# ina226.net
KiCad netlist of a schematic drawn in Altium Designer
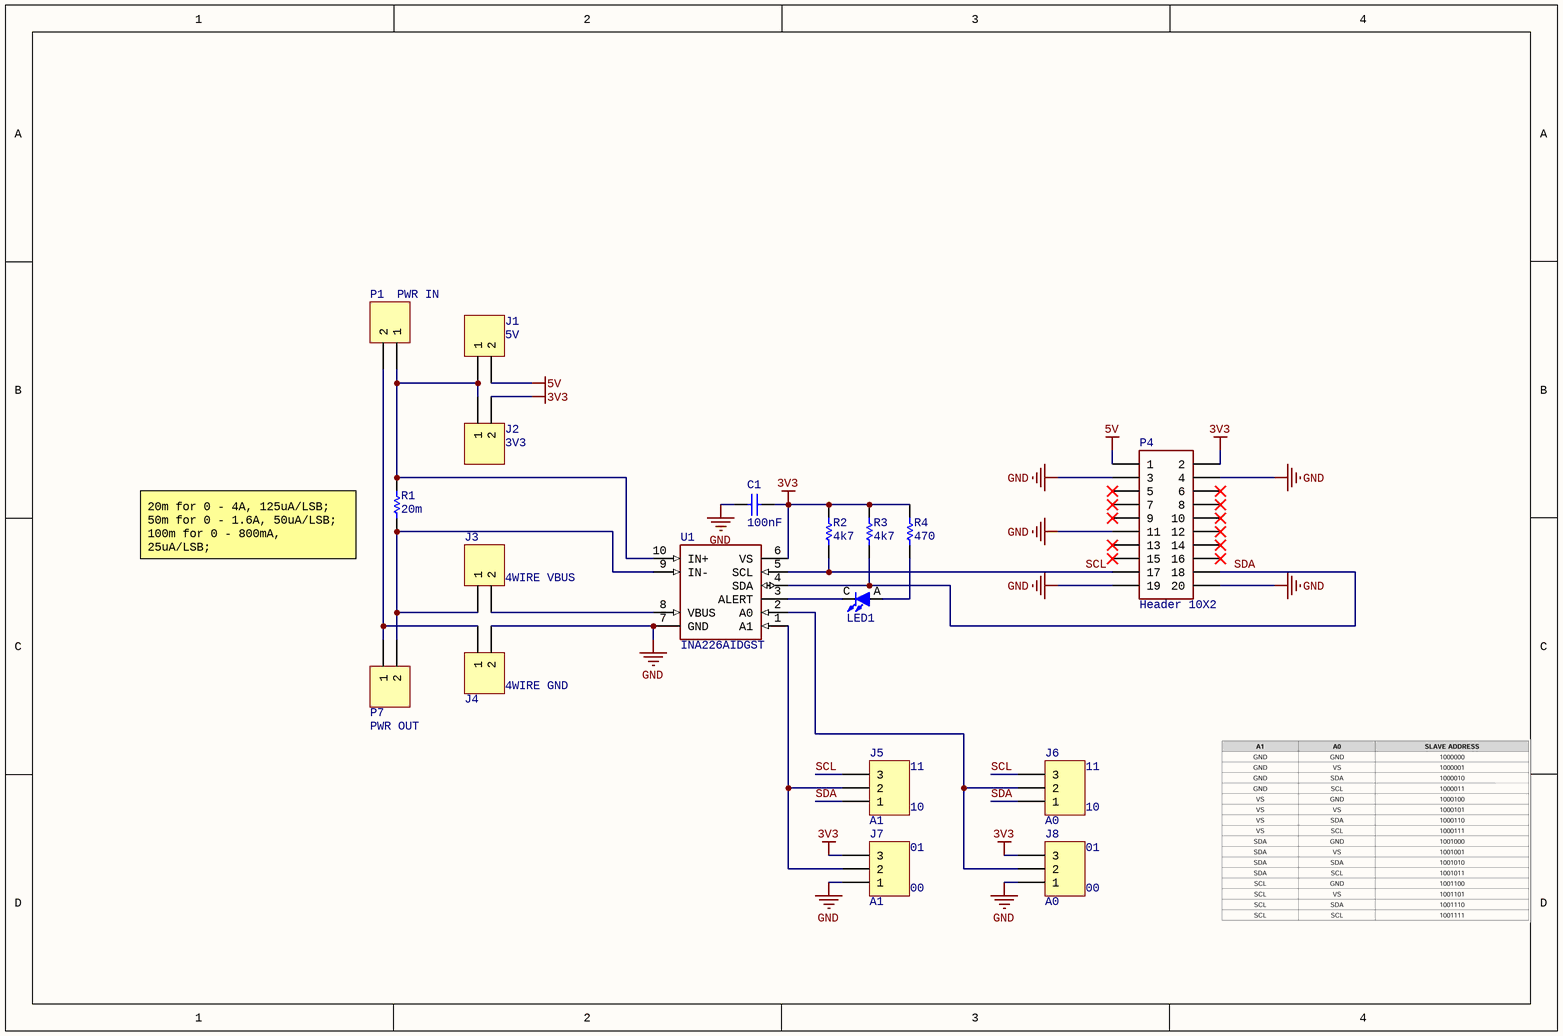
[diagram p0: ina226.SchDoc]

(export (version "E")
  (design (tool "Eeschema 10.0.6"))
  (components
    (comp (ref "C1")
      (value "100nF")
      (footprint "footprints:CAPC100X50X55L25N")
      (description "Capacitor (Semiconductor SIM Model)")
      (fields (field (name "PUBLISHER") "Altium Limited"))
      (libsource (lib "Miscellaneous Devices") (part "Cap Semi"))
    )
    (comp (ref "J1")
      (value "5V")
      (footprint "HDR1X2")
      (description "Header, 2-Pin")
      (fields (field (name "PUBLISHER") "Altium Limited"))
      (libsource (lib "Miscellaneous Connectors") (part "Header 2"))
    )
    (comp (ref "J2")
      (value "3V3")
      (footprint "HDR1X2")
      (description "Header, 2-Pin")
      (fields (field (name "PUBLISHER") "Altium Limited"))
      (libsource (lib "") (part "Header 2_2"))
    )
    (comp (ref "J3")
      (value "4WIRE VBUS")
      (footprint "HDR1X2")
      (description "Header, 2-Pin")
      (fields (field (name "PUBLISHER") "Altium Limited"))
      (libsource (lib "Miscellaneous Connectors") (part "Header 2"))
    )
    (comp (ref "J4")
      (value "4WIRE GND")
      (footprint "HDR1X2")
      (description "Header, 2-Pin")
      (fields (field (name "PUBLISHER") "Altium Limited"))
      (libsource (lib "") (part "Header 2_2"))
    )
    (comp (ref "J5")
      (value "A1")
      (footprint "HDR1X3")
      (description "Header, 3-Pin")
      (fields (field (name "PUBLISHER") "Altium Limited"))
      (libsource (lib "Miscellaneous Connectors") (part "Header 3"))
    )
    (comp (ref "J6")
      (value "A0")
      (footprint "HDR1X3")
      (description "Header, 3-Pin")
      (fields (field (name "PUBLISHER") "Altium Limited"))
      (libsource (lib "Miscellaneous Connectors") (part "Header 3"))
    )
    (comp (ref "J7")
      (value "A1")
      (footprint "HDR1X3")
      (description "Header, 3-Pin")
      (fields (field (name "PUBLISHER") "Altium Limited"))
      (libsource (lib "Miscellaneous Connectors") (part "Header 3"))
    )
    (comp (ref "J8")
      (value "A0")
      (footprint "HDR1X3")
      (description "Header, 3-Pin")
      (fields (field (name "PUBLISHER") "Altium Limited"))
      (libsource (lib "Miscellaneous Connectors") (part "Header 3"))
    )
    (comp (ref "LED1")
      (value "蓝灯 正贴")
      (footprint "footprints:LEDC100X50X45L25N")
      (description "贴片LED")
      (libsource (lib "mcontroller") (part "LED-SMD"))
    )
    (comp (ref "P1")
      (value "PWR IN")
      (footprint "footprints:CONN-TH_P3.50_KF250-3.5-2P-1")
      (description "Header, 2-Pin")
      (fields (field (name "PUBLISHER") "Altium Limited"))
      (libsource (lib "") (part "Header 2_1"))
    )
    (comp (ref "P4")
      (value "Header 10X2")
      (footprint "footprints:HDRV20W63P254_10X2_2540X508H860")
      (description "Header, 10-Pin, Dual row")
      (libsource (lib "Sch") (part "Header 10X2"))
    )
    (comp (ref "P7")
      (value "PWR OUT")
      (footprint "footprints:CONN-TH_P3.50_KF250-3.5-2P-1")
      (description "Header, 2-Pin")
      (fields (field (name "PUBLISHER") "Altium Limited"))
      (libsource (lib "") (part "Header 2_2"))
    )
    (comp (ref "R1")
      (value "20m")
      (footprint "footprints:RESC620X325X80L80N-K")
      (description "Resistor")
      (libsource (lib "Miscellaneous Devices") (part "Res1"))
    )
    (comp (ref "R2")
      (value "4k7")
      (footprint "footprints:RESC100X50X35L25N")
      (description "Resistor")
      (fields (field (name "PUBLISHER") "Altium Limited"))
      (libsource (lib "Miscellaneous Devices") (part "Res1"))
    )
    (comp (ref "R3")
      (value "4k7")
      (footprint "footprints:RESC100X50X35L25N")
      (description "Resistor")
      (fields (field (name "PUBLISHER") "Altium Limited"))
      (libsource (lib "Miscellaneous Devices") (part "Res1"))
    )
    (comp (ref "R4")
      (value "470")
      (footprint "footprints:RESC100X50X35L25N")
      (description "Resistor")
      (fields (field (name "PUBLISHER") "Altium Limited"))
      (libsource (lib "Miscellaneous Devices") (part "Res1"))
    )
    (comp (ref "U1")
      (value "INA226AIDGST")
      (footprint "footprints:DGS0010A_N")
      (libsource (lib "Sch") (part "CMP-0704-00057-2"))
    )
  )
  (nets
    (net (code "1") (name "/SCL") (class "Default")
      (node (ref "J5") (pin "3") (pinfunction "3_3") (pintype "passive"))
      (node (ref "J6") (pin "3") (pinfunction "3_3") (pintype "passive"))
      (node (ref "P4") (pin "17") (pinfunction "17_17") (pintype "passive"))
      (node (ref "R2") (pin "1") (pinfunction "1_1") (pintype "passive"))
      (node (ref "U1") (pin "5") (pinfunction "SCL_5") (pintype "input"))
    )
    (net (code "2") (name "/SDA") (class "Default")
      (node (ref "J5") (pin "1") (pinfunction "1_1") (pintype "passive"))
      (node (ref "J6") (pin "1") (pinfunction "1_1") (pintype "passive"))
      (node (ref "P4") (pin "18") (pinfunction "18_18") (pintype "passive"))
      (node (ref "R3") (pin "1") (pinfunction "1_1") (pintype "passive"))
      (node (ref "U1") (pin "4") (pinfunction "SDA_4") (pintype "bidirectional"))
    )
    (net (code "3") (name "3V3") (class "Default")
      (node (ref "C1") (pin "2") (pinfunction "2_2") (pintype "passive"))
      (node (ref "J2") (pin "2") (pinfunction "2_2") (pintype "passive"))
      (node (ref "J7") (pin "3") (pinfunction "3_3") (pintype "passive"))
      (node (ref "J8") (pin "3") (pinfunction "3_3") (pintype "passive"))
      (node (ref "P4") (pin "2") (pinfunction "2_2") (pintype "passive"))
      (node (ref "R2") (pin "2") (pinfunction "2_2") (pintype "passive"))
      (node (ref "R3") (pin "2") (pinfunction "2_2") (pintype "passive"))
      (node (ref "R4") (pin "2") (pinfunction "2_2") (pintype "passive"))
      (node (ref "U1") (pin "6") (pinfunction "VS_6") (pintype "power_in"))
    )
    (net (code "4") (name "5V") (class "Default")
      (node (ref "J1") (pin "2") (pinfunction "2_2") (pintype "passive"))
      (node (ref "P4") (pin "1") (pinfunction "1_1") (pintype "passive"))
    )
    (net (code "5") (name "GND") (class "Default")
      (node (ref "C1") (pin "1") (pinfunction "1_1") (pintype "passive"))
      (node (ref "J4") (pin "2") (pinfunction "2_2") (pintype "passive"))
      (node (ref "J7") (pin "1") (pinfunction "1_1") (pintype "passive"))
      (node (ref "J8") (pin "1") (pinfunction "1_1") (pintype "passive"))
      (node (ref "P4") (pin "11") (pinfunction "11_11") (pintype "passive"))
      (node (ref "P4") (pin "19") (pinfunction "19_19") (pintype "passive"))
      (node (ref "P4") (pin "20") (pinfunction "20_20") (pintype "passive"))
      (node (ref "P4") (pin "3") (pinfunction "3_3") (pintype "passive"))
      (node (ref "P4") (pin "4") (pinfunction "4_4") (pintype "passive"))
      (node (ref "U1") (pin "7") (pinfunction "GND_7") (pintype "power_in"))
    )
    (net (code "6") (name "Net-(J4-Pad1)") (class "Default")
      (node (ref "J4") (pin "1") (pinfunction "1_1") (pintype "passive"))
      (node (ref "P1") (pin "2") (pinfunction "2_2") (pintype "passive"))
      (node (ref "P7") (pin "1") (pinfunction "1_1") (pintype "passive"))
    )
    (net (code "7") (name "Net-(LED1-K)") (class "Default")
      (node (ref "LED1") (pin "C") (pinfunction "K_C") (pintype "passive"))
      (node (ref "U1") (pin "3") (pinfunction "ALERT_3") (pintype "open_collector"))
    )
    (net (code "8") (name "Net-(LED1-PadA)") (class "Default")
      (node (ref "LED1") (pin "A") (pinfunction "A_A") (pintype "passive"))
      (node (ref "R4") (pin "1") (pinfunction "1_1") (pintype "passive"))
    )
    (net (code "9") (name "Net-(U1-A0)") (class "Default")
      (node (ref "J6") (pin "2") (pinfunction "2_2") (pintype "passive"))
      (node (ref "J8") (pin "2") (pinfunction "2_2") (pintype "passive"))
      (node (ref "U1") (pin "2") (pinfunction "A0_2") (pintype "input"))
    )
    (net (code "10") (name "Net-(U1-A1)") (class "Default")
      (node (ref "J5") (pin "2") (pinfunction "2_2") (pintype "passive"))
      (node (ref "J7") (pin "2") (pinfunction "2_2") (pintype "passive"))
      (node (ref "U1") (pin "1") (pinfunction "A1_1") (pintype "input"))
    )
    (net (code "11") (name "Net-(U1-IN+)") (class "Default")
      (node (ref "J1") (pin "1") (pinfunction "1_1") (pintype "passive"))
      (node (ref "J2") (pin "1") (pinfunction "1_1") (pintype "passive"))
      (node (ref "P1") (pin "1") (pinfunction "1_1") (pintype "passive"))
      (node (ref "R1") (pin "2") (pinfunction "2_2") (pintype "passive"))
      (node (ref "U1") (pin "10") (pinfunction "IN+_10") (pintype "input"))
    )
    (net (code "12") (name "Net-(U1-IN-)") (class "Default")
      (node (ref "J3") (pin "1") (pinfunction "1_1") (pintype "passive"))
      (node (ref "P7") (pin "2") (pinfunction "2_2") (pintype "passive"))
      (node (ref "R1") (pin "1") (pinfunction "1_1") (pintype "passive"))
      (node (ref "U1") (pin "9") (pinfunction "IN-_9") (pintype "input"))
    )
    (net (code "13") (name "Net-(U1-VBUS)") (class "Default")
      (node (ref "J3") (pin "2") (pinfunction "2_2") (pintype "passive"))
      (node (ref "U1") (pin "8") (pinfunction "VBUS_8") (pintype "input"))
    )
    (net (code "14") (name "unconnected-(P4-Pad5)") (class "Default")
      (node (ref "P4") (pin "5") (pinfunction "5_5") (pintype "passive+no_connect"))
    )
    (net (code "15") (name "unconnected-(P4-Pad6)") (class "Default")
      (node (ref "P4") (pin "6") (pinfunction "6_6") (pintype "passive+no_connect"))
    )
    (net (code "16") (name "unconnected-(P4-Pad7)") (class "Default")
      (node (ref "P4") (pin "7") (pinfunction "7_7") (pintype "passive+no_connect"))
    )
    (net (code "17") (name "unconnected-(P4-Pad8)") (class "Default")
      (node (ref "P4") (pin "8") (pinfunction "8_8") (pintype "passive+no_connect"))
    )
    (net (code "18") (name "unconnected-(P4-Pad9)") (class "Default")
      (node (ref "P4") (pin "9") (pinfunction "9_9") (pintype "passive+no_connect"))
    )
    (net (code "19") (name "unconnected-(P4-Pad10)") (class "Default")
      (node (ref "P4") (pin "10") (pinfunction "10_10") (pintype "passive+no_connect"))
    )
    (net (code "20") (name "unconnected-(P4-Pad12)") (class "Default")
      (node (ref "P4") (pin "12") (pinfunction "12_12") (pintype "passive+no_connect"))
    )
    (net (code "21") (name "unconnected-(P4-Pad13)") (class "Default")
      (node (ref "P4") (pin "13") (pinfunction "13_13") (pintype "passive+no_connect"))
    )
    (net (code "22") (name "unconnected-(P4-Pad14)") (class "Default")
      (node (ref "P4") (pin "14") (pinfunction "14_14") (pintype "passive+no_connect"))
    )
    (net (code "23") (name "unconnected-(P4-Pad15)") (class "Default")
      (node (ref "P4") (pin "15") (pinfunction "15_15") (pintype "passive+no_connect"))
    )
    (net (code "24") (name "unconnected-(P4-Pad16)") (class "Default")
      (node (ref "P4") (pin "16") (pinfunction "16_16") (pintype "passive+no_connect"))
    )
  )
)
